# HC-SR501.net
KiCad netlist of a schematic drawn in Altium Designer
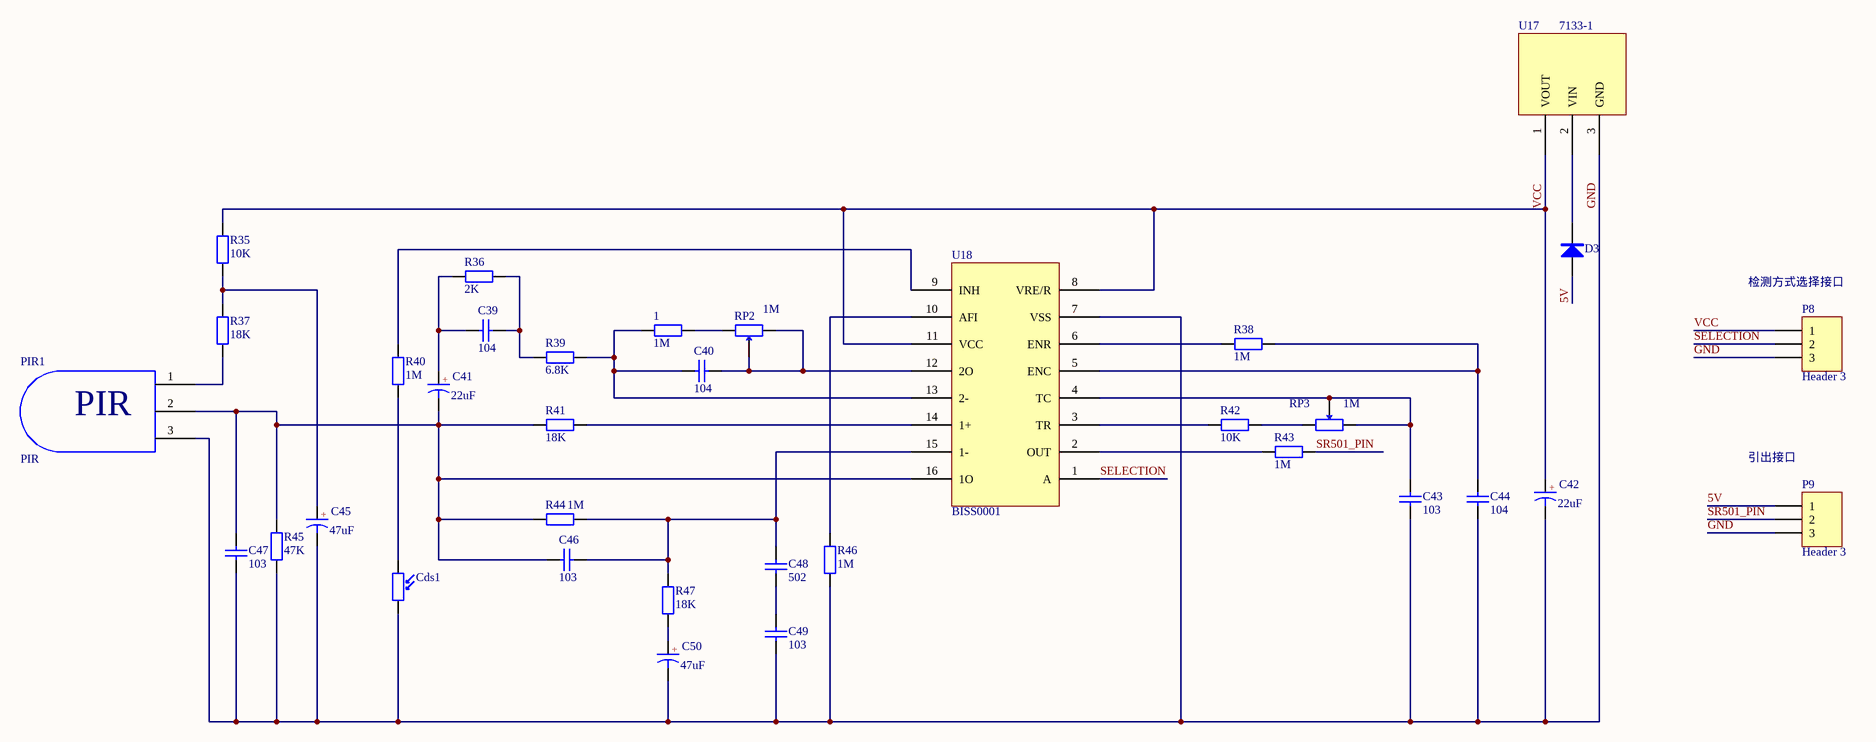
[diagram p0: HC-SR501.SchDoc]

(export (version "E")
  (design (tool "Eeschema 10.0.6"))
  (components
    (comp (ref "1")
      (value "1M")
      (footprint "R0805_L")
      (description "贴片电阻")
      (libsource (lib "0.1 - 电阻-电容-电感-保险丝-晶振-晶体-磁珠-电位器-法拉电容-馈通电容") (part "R"))
    )
    (comp (ref "C39")
      (value "104")
      (footprint "C0805_L")
      (description "贴片电容/MLCC电容")
      (libsource (lib "0.1 - 电阻-电容-电感-保险丝-晶振-晶体-磁珠-电位器-法拉电容-馈通电容") (part "C"))
    )
    (comp (ref "C40")
      (value "104")
      (footprint "C0805_L")
      (description "贴片电容/MLCC电容")
      (libsource (lib "0.1 - 电阻-电容-电感-保险丝-晶振-晶体-磁珠-电位器-法拉电容-馈通电容") (part "C"))
    )
    (comp (ref "C41")
      (value "22uF")
      (footprint "CE-1.5*4*8")
      (description "直插电解电容")
      (libsource (lib "0.1 - 电阻-电容-电感-保险丝-晶振-晶体-磁珠-电位器-法拉电容-馈通电容") (part "CE"))
    )
    (comp (ref "C42")
      (value "22uF")
      (footprint "CE-1.5*4*8")
      (description "直插电解电容")
      (libsource (lib "0.1 - 电阻-电容-电感-保险丝-晶振-晶体-磁珠-电位器-法拉电容-馈通电容") (part "CE"))
    )
    (comp (ref "C43")
      (value "103")
      (footprint "C0805_L")
      (description "贴片电容/MLCC电容")
      (libsource (lib "0.1 - 电阻-电容-电感-保险丝-晶振-晶体-磁珠-电位器-法拉电容-馈通电容") (part "C"))
    )
    (comp (ref "C44")
      (value "104")
      (footprint "C0805_L")
      (description "贴片电容/MLCC电容")
      (libsource (lib "0.1 - 电阻-电容-电感-保险丝-晶振-晶体-磁珠-电位器-法拉电容-馈通电容") (part "C"))
    )
    (comp (ref "C45")
      (value "47uF")
      (footprint "CE-1.5*4*8")
      (description "直插电解电容")
      (libsource (lib "0.1 - 电阻-电容-电感-保险丝-晶振-晶体-磁珠-电位器-法拉电容-馈通电容") (part "CE"))
    )
    (comp (ref "C46")
      (value "103")
      (footprint "C0805_L")
      (description "贴片电容/MLCC电容")
      (libsource (lib "0.1 - 电阻-电容-电感-保险丝-晶振-晶体-磁珠-电位器-法拉电容-馈通电容") (part "C"))
    )
    (comp (ref "C47")
      (value "103")
      (footprint "C0805_L")
      (description "贴片电容/MLCC电容")
      (libsource (lib "0.1 - 电阻-电容-电感-保险丝-晶振-晶体-磁珠-电位器-法拉电容-馈通电容") (part "C"))
    )
    (comp (ref "C48")
      (value "502")
      (footprint "C0805_L")
      (description "贴片电容/MLCC电容")
      (libsource (lib "0.1 - 电阻-电容-电感-保险丝-晶振-晶体-磁珠-电位器-法拉电容-馈通电容") (part "C"))
    )
    (comp (ref "C49")
      (value "103")
      (footprint "C0805_L")
      (description "贴片电容/MLCC电容")
      (libsource (lib "0.1 - 电阻-电容-电感-保险丝-晶振-晶体-磁珠-电位器-法拉电容-馈通电容") (part "C"))
    )
    (comp (ref "C50")
      (value "47uF")
      (footprint "CE-1.5*4*8")
      (description "直插电解电容")
      (libsource (lib "0.1 - 电阻-电容-电感-保险丝-晶振-晶体-磁珠-电位器-法拉电容-馈通电容") (part "CE"))
    )
    (comp (ref "Cds1")
      (value "10K")
      (footprint "RG5528")
      (description "光敏电阻")
      (libsource (lib "0.1 - 电阻-电容-电感-保险丝-晶振-晶体-磁珠-电位器-法拉电容-馈通电容") (part "RG5516"))
    )
    (comp (ref "D3")
      (value "M7")
      (footprint "SMA")
      (description "整流二极管")
      (libsource (lib "0.2 - 二极管-TVS-ESD-整流桥-放电管") (part "M7"))
    )
    (comp (ref "P8")
      (value "Header 3")
      (footprint "HDR1X3")
      (description "Header, 3-Pin")
      (fields (field (name "PUBLISHER") "Altium Limited"))
      (libsource (lib "Miscellaneous Connectors") (part "Header 3"))
    )
    (comp (ref "P9")
      (value "Header 3")
      (footprint "HDR1X3")
      (description "Header, 3-Pin")
      (fields (field (name "PUBLISHER") "Altium Limited"))
      (libsource (lib "Miscellaneous Connectors") (part "Header 3"))
    )
    (comp (ref "PIR1") (value "PIR") (description "热释电传感器") (libsource (lib "HC-SR501") (part "PIR")))
    (comp (ref "R35")
      (value "10K")
      (footprint "R0805_L")
      (description "贴片电阻")
      (libsource (lib "0.1 - 电阻-电容-电感-保险丝-晶振-晶体-磁珠-电位器-法拉电容-馈通电容") (part "R"))
    )
    (comp (ref "R36")
      (value "2K")
      (footprint "R0805_L")
      (description "贴片电阻")
      (libsource (lib "0.1 - 电阻-电容-电感-保险丝-晶振-晶体-磁珠-电位器-法拉电容-馈通电容") (part "R"))
    )
    (comp (ref "R37")
      (value "18K")
      (footprint "R0805_L")
      (description "贴片电阻")
      (libsource (lib "0.1 - 电阻-电容-电感-保险丝-晶振-晶体-磁珠-电位器-法拉电容-馈通电容") (part "R"))
    )
    (comp (ref "R38")
      (value "1M")
      (footprint "R0805_L")
      (description "贴片电阻")
      (libsource (lib "0.1 - 电阻-电容-电感-保险丝-晶振-晶体-磁珠-电位器-法拉电容-馈通电容") (part "R"))
    )
    (comp (ref "R39")
      (value "6.8K")
      (footprint "R0805_L")
      (description "贴片电阻")
      (libsource (lib "0.1 - 电阻-电容-电感-保险丝-晶振-晶体-磁珠-电位器-法拉电容-馈通电容") (part "R"))
    )
    (comp (ref "R40")
      (value "1M")
      (footprint "R0805_L")
      (description "贴片电阻")
      (libsource (lib "0.1 - 电阻-电容-电感-保险丝-晶振-晶体-磁珠-电位器-法拉电容-馈通电容") (part "R"))
    )
    (comp (ref "R41")
      (value "18K")
      (footprint "R0805_L")
      (description "贴片电阻")
      (libsource (lib "0.1 - 电阻-电容-电感-保险丝-晶振-晶体-磁珠-电位器-法拉电容-馈通电容") (part "R"))
    )
    (comp (ref "R42")
      (value "10K")
      (footprint "R0805_L")
      (description "贴片电阻")
      (libsource (lib "0.1 - 电阻-电容-电感-保险丝-晶振-晶体-磁珠-电位器-法拉电容-馈通电容") (part "R"))
    )
    (comp (ref "R43")
      (value "1M")
      (footprint "R0805_L")
      (description "贴片电阻")
      (libsource (lib "0.1 - 电阻-电容-电感-保险丝-晶振-晶体-磁珠-电位器-法拉电容-馈通电容") (part "R"))
    )
    (comp (ref "R44")
      (value "1M")
      (footprint "R0805_L")
      (description "贴片电阻")
      (libsource (lib "0.1 - 电阻-电容-电感-保险丝-晶振-晶体-磁珠-电位器-法拉电容-馈通电容") (part "R"))
    )
    (comp (ref "R45")
      (value "47K")
      (footprint "R0805_L")
      (description "贴片电阻")
      (libsource (lib "0.1 - 电阻-电容-电感-保险丝-晶振-晶体-磁珠-电位器-法拉电容-馈通电容") (part "R"))
    )
    (comp (ref "R46")
      (value "1M")
      (footprint "R0805_L")
      (description "贴片电阻")
      (libsource (lib "0.1 - 电阻-电容-电感-保险丝-晶振-晶体-磁珠-电位器-法拉电容-馈通电容") (part "R"))
    )
    (comp (ref "R47")
      (value "18K")
      (footprint "R0805_L")
      (description "贴片电阻")
      (libsource (lib "0.1 - 电阻-电容-电感-保险丝-晶振-晶体-磁珠-电位器-法拉电容-馈通电容") (part "R"))
    )
    (comp (ref "RP2")
      (value "1M")
      (footprint "3296W")
      (description "单联电位器")
      (libsource (lib "0.1 - 电阻-电容-电感-保险丝-晶振-晶体-磁珠-电位器-法拉电容-馈通电容") (part "RP"))
    )
    (comp (ref "RP3")
      (value "1M")
      (footprint "3296W")
      (description "单联电位器")
      (libsource (lib "0.1 - 电阻-电容-电感-保险丝-晶振-晶体-磁珠-电位器-法拉电容-馈通电容") (part "RP"))
    )
    (comp (ref "U17") (value "7133-1") (description "稳压芯片") (libsource (lib "HC-SR501") (part "7133-1")))
    (comp (ref "U18")
      (value "BISS0001")
      (description "传感信号处理集成电路")
      (libsource (lib "HC-SR501") (part "BISS0001"))
    )
  )
  (nets
    (net (code "1") (name "/5V") (class "Default")
      (node (ref "D3") (pin "1") (pinfunction "A_1") (pintype "passive"))
      (node (ref "P9") (pin "1") (pinfunction "1_1") (pintype "passive"))
    )
    (net (code "2") (name "/GND") (class "Default")
      (node (ref "C42") (pin "2") (pinfunction "2_2") (pintype "passive"))
      (node (ref "C43") (pin "2") (pinfunction "2_2") (pintype "passive"))
      (node (ref "C44") (pin "2") (pinfunction "2_2") (pintype "passive"))
      (node (ref "C45") (pin "2") (pinfunction "2_2") (pintype "passive"))
      (node (ref "C47") (pin "1") (pinfunction "1_1") (pintype "passive"))
      (node (ref "C49") (pin "2") (pinfunction "2_2") (pintype "passive"))
      (node (ref "C50") (pin "2") (pinfunction "2_2") (pintype "passive"))
      (node (ref "Cds1") (pin "2") (pinfunction "2_2") (pintype "passive"))
      (node (ref "P8") (pin "3") (pinfunction "3_3") (pintype "passive"))
      (node (ref "P9") (pin "3") (pinfunction "3_3") (pintype "passive"))
      (node (ref "PIR1") (pin "3") (pintype "passive"))
      (node (ref "R45") (pin "1") (pinfunction "1_1") (pintype "passive"))
      (node (ref "R46") (pin "1") (pinfunction "1_1") (pintype "passive"))
      (node (ref "U17") (pin "3") (pinfunction "GND_3") (pintype "passive"))
      (node (ref "U18") (pin "7") (pinfunction "VSS_7") (pintype "passive"))
    )
    (net (code "3") (name "/SELECTION") (class "Default")
      (node (ref "P8") (pin "2") (pinfunction "2_2") (pintype "passive"))
      (node (ref "U18") (pin "1") (pinfunction "A_1") (pintype "passive"))
    )
    (net (code "4") (name "/SR501_PIN") (class "Default")
      (node (ref "P9") (pin "2") (pinfunction "2_2") (pintype "passive"))
      (node (ref "R43") (pin "1") (pinfunction "1_1") (pintype "passive"))
    )
    (net (code "5") (name "/VCC") (class "Default")
      (node (ref "C42") (pin "1") (pinfunction "1_1") (pintype "passive"))
      (node (ref "P8") (pin "1") (pinfunction "1_1") (pintype "passive"))
      (node (ref "R35") (pin "2") (pinfunction "2_2") (pintype "passive"))
      (node (ref "U17") (pin "1") (pinfunction "VOUT_1") (pintype "passive"))
      (node (ref "U18") (pin "11") (pinfunction "VCC_11") (pintype "passive"))
      (node (ref "U18") (pin "8") (pinfunction "VRE/R_8") (pintype "passive"))
    )
    (net (code "6") (name "Net-(1-Pad1)") (class "Default")
      (node (ref "1") (pin "1") (pinfunction "1_1") (pintype "passive"))
      (node (ref "RP2") (pin "3") (pinfunction "3_3") (pintype "passive"))
    )
    (net (code "7") (name "Net-(C39-Pad1)") (class "Default")
      (node (ref "C39") (pin "1") (pinfunction "1_1") (pintype "passive"))
      (node (ref "R36") (pin "1") (pinfunction "1_1") (pintype "passive"))
      (node (ref "R39") (pin "2") (pinfunction "2_2") (pintype "passive"))
    )
    (net (code "8") (name "Net-(C39-Pad2)") (class "Default")
      (node (ref "C39") (pin "2") (pinfunction "2_2") (pintype "passive"))
      (node (ref "C41") (pin "1") (pinfunction "1_1") (pintype "passive"))
      (node (ref "R36") (pin "2") (pinfunction "2_2") (pintype "passive"))
    )
    (net (code "9") (name "Net-(C45-Pad1)") (class "Default")
      (node (ref "C45") (pin "1") (pinfunction "1_1") (pintype "passive"))
      (node (ref "R35") (pin "1") (pinfunction "1_1") (pintype "passive"))
      (node (ref "R37") (pin "2") (pinfunction "2_2") (pintype "passive"))
    )
    (net (code "10") (name "Net-(C48-Pad2)") (class "Default")
      (node (ref "C48") (pin "2") (pinfunction "2_2") (pintype "passive"))
      (node (ref "C49") (pin "1") (pinfunction "1_1") (pintype "passive"))
    )
    (net (code "11") (name "Net-(C50-Pad1)") (class "Default")
      (node (ref "C50") (pin "1") (pinfunction "1_1") (pintype "passive"))
      (node (ref "R47") (pin "2") (pinfunction "2_2") (pintype "passive"))
    )
    (net (code "12") (name "Net-(Cds1-Pad1)") (class "Default")
      (node (ref "Cds1") (pin "1") (pinfunction "1_1") (pintype "passive"))
      (node (ref "R40") (pin "1") (pinfunction "1_1") (pintype "passive"))
    )
    (net (code "13") (name "Net-(D3-K)") (class "Default")
      (node (ref "D3") (pin "2") (pinfunction "K_2") (pintype "passive"))
      (node (ref "U17") (pin "2") (pinfunction "VIN_2") (pintype "passive"))
    )
    (net (code "14") (name "Net-(PIR1-VIN)") (class "Default")
      (node (ref "PIR1") (pin "1") (pinfunction "VIN_1") (pintype "passive"))
      (node (ref "R37") (pin "1") (pinfunction "1_1") (pintype "passive"))
    )
    (net (code "15") (name "Net-(R42-Pad1)") (class "Default")
      (node (ref "R42") (pin "1") (pinfunction "1_1") (pintype "passive"))
      (node (ref "RP3") (pin "1") (pinfunction "1_1") (pintype "passive"))
    )
    (net (code "16") (name "Net-(U18-1+)") (class "Default")
      (node (ref "R41") (pin "1") (pinfunction "1_1") (pintype "passive"))
      (node (ref "U18") (pin "14") (pinfunction "1+_14") (pintype "passive"))
    )
    (net (code "17") (name "Net-(U18-1-)") (class "Default")
      (node (ref "C46") (pin "1") (pinfunction "1_1") (pintype "passive"))
      (node (ref "C48") (pin "1") (pinfunction "1_1") (pintype "passive"))
      (node (ref "R44") (pin "1") (pinfunction "1_1") (pintype "passive"))
      (node (ref "R47") (pin "1") (pinfunction "1_1") (pintype "passive"))
      (node (ref "U18") (pin "15") (pinfunction "1-_15") (pintype "passive"))
    )
    (net (code "18") (name "Net-(U18-1O)") (class "Default")
      (node (ref "C41") (pin "2") (pinfunction "2_2") (pintype "passive"))
      (node (ref "C46") (pin "2") (pinfunction "2_2") (pintype "passive"))
      (node (ref "C47") (pin "2") (pinfunction "2_2") (pintype "passive"))
      (node (ref "PIR1") (pin "2") (pintype "passive"))
      (node (ref "R41") (pin "2") (pinfunction "2_2") (pintype "passive"))
      (node (ref "R44") (pin "2") (pinfunction "2_2") (pintype "passive"))
      (node (ref "R45") (pin "2") (pinfunction "2_2") (pintype "passive"))
      (node (ref "U18") (pin "16") (pinfunction "1O_16") (pintype "passive"))
    )
    (net (code "19") (name "Net-(U18-2-)") (class "Default")
      (node (ref "1") (pin "2") (pinfunction "2_2") (pintype "passive"))
      (node (ref "C40") (pin "2") (pinfunction "2_2") (pintype "passive"))
      (node (ref "R39") (pin "1") (pinfunction "1_1") (pintype "passive"))
      (node (ref "U18") (pin "13") (pinfunction "2-_13") (pintype "passive"))
    )
    (net (code "20") (name "Net-(U18-2O)") (class "Default")
      (node (ref "C40") (pin "1") (pinfunction "1_1") (pintype "passive"))
      (node (ref "RP2") (pin "1") (pinfunction "1_1") (pintype "passive"))
      (node (ref "RP2") (pin "2") (pinfunction "2_2") (pintype "passive"))
      (node (ref "U18") (pin "12") (pinfunction "2O_12") (pintype "passive"))
    )
    (net (code "21") (name "Net-(U18-AFI)") (class "Default")
      (node (ref "R46") (pin "2") (pinfunction "2_2") (pintype "passive"))
      (node (ref "U18") (pin "10") (pinfunction "AFI_10") (pintype "passive"))
    )
    (net (code "22") (name "Net-(U18-ENC)") (class "Default")
      (node (ref "C44") (pin "1") (pinfunction "1_1") (pintype "passive"))
      (node (ref "R38") (pin "1") (pinfunction "1_1") (pintype "passive"))
      (node (ref "U18") (pin "5") (pinfunction "ENC_5") (pintype "passive"))
    )
    (net (code "23") (name "Net-(U18-ENR)") (class "Default")
      (node (ref "R38") (pin "2") (pinfunction "2_2") (pintype "passive"))
      (node (ref "U18") (pin "6") (pinfunction "ENR_6") (pintype "passive"))
    )
    (net (code "24") (name "Net-(U18-INH)") (class "Default")
      (node (ref "R40") (pin "2") (pinfunction "2_2") (pintype "passive"))
      (node (ref "U18") (pin "9") (pinfunction "INH_9") (pintype "passive"))
    )
    (net (code "25") (name "Net-(U18-OUT)") (class "Default")
      (node (ref "R43") (pin "2") (pinfunction "2_2") (pintype "passive"))
      (node (ref "U18") (pin "2") (pinfunction "OUT_2") (pintype "passive"))
    )
    (net (code "26") (name "Net-(U18-TC)") (class "Default")
      (node (ref "C43") (pin "1") (pinfunction "1_1") (pintype "passive"))
      (node (ref "RP3") (pin "2") (pinfunction "2_2") (pintype "passive"))
      (node (ref "RP3") (pin "3") (pinfunction "3_3") (pintype "passive"))
      (node (ref "U18") (pin "4") (pinfunction "TC_4") (pintype "passive"))
    )
    (net (code "27") (name "Net-(U18-TR)") (class "Default")
      (node (ref "R42") (pin "2") (pinfunction "2_2") (pintype "passive"))
      (node (ref "U18") (pin "3") (pinfunction "TR_3") (pintype "passive"))
    )
  )
)
